# PicCan2.net
KiCad netlist of a schematic drawn in EAGLE
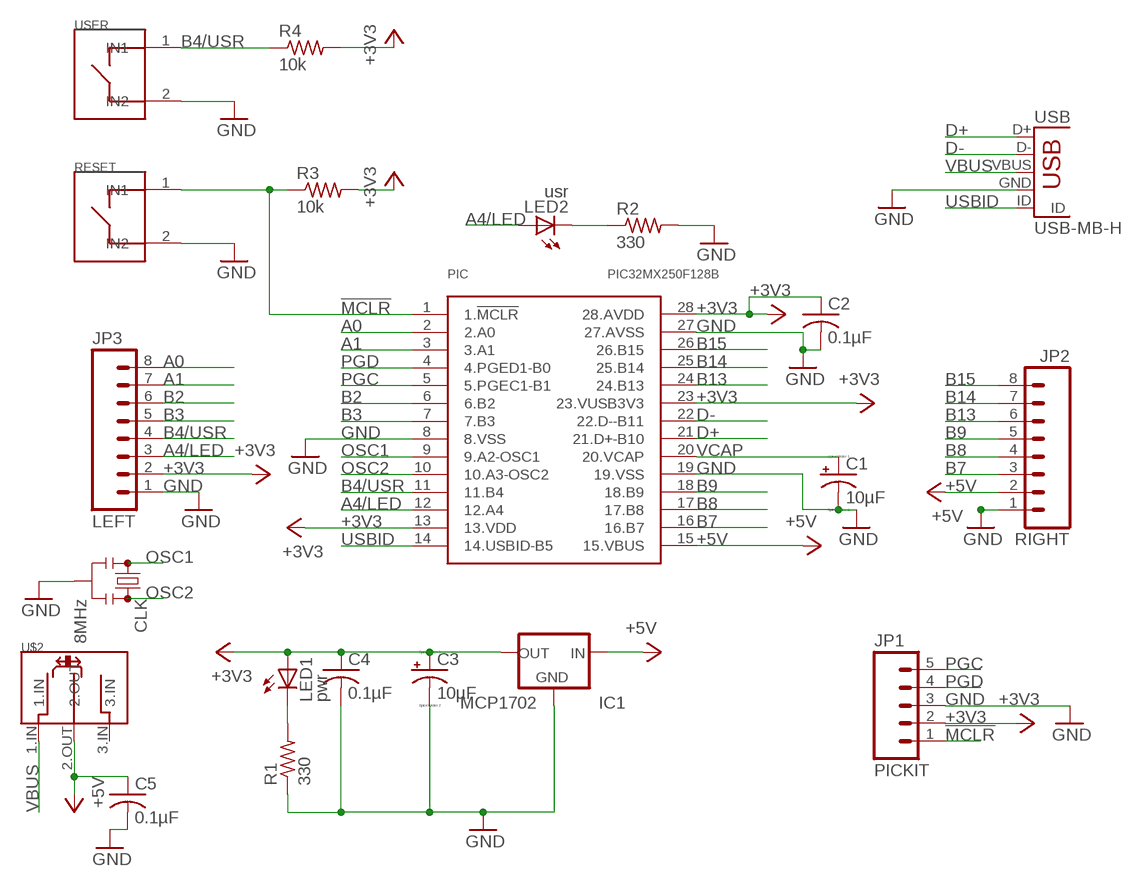
[diagram p0: schematic, sheet 1]

(export (version "E")
  (design (tool "Eeschema 10.0.6"))
  (components
    (comp (ref "C1")
      (value "10µF")
      (footprint "eagle-import:B45181A")
      (libsource (lib "eagle-import") (part "CPOL-USB45181A"))
    )
    (comp (ref "C2")
      (value "0.1µF")
      (footprint "eagle-import:C025-025X050")
      (libsource (lib "eagle-import") (part "C-US025-025X050"))
    )
    (comp (ref "C3")
      (value "10µF")
      (footprint "eagle-import:B45181A")
      (libsource (lib "eagle-import") (part "CPOL-USB45181A"))
    )
    (comp (ref "C4")
      (value "0.1µF")
      (footprint "eagle-import:C025-025X050")
      (libsource (lib "eagle-import") (part "C-US025-025X050"))
    )
    (comp (ref "C5")
      (value "0.1µF")
      (footprint "eagle-import:C025-025X050")
      (libsource (lib "eagle-import") (part "C-US025-025X050"))
    )
    (comp (ref "CLK")
      (value "8MHz")
      (footprint "eagle-import:RESONATOR-PTH")
      (libsource (lib "eagle-import") (part "RESONATORPTH"))
    )
    (comp (ref "IC1")
      (value "MCP1702")
      (footprint "eagle-import:79LXX")
      (libsource (lib "eagle-import") (part "79LXX"))
    )
    (comp (ref "JP1")
      (value "PICKIT")
      (footprint "eagle-import:1X05")
      (libsource (lib "eagle-import") (part "M05PTH"))
    )
    (comp (ref "JP2")
      (value "RIGHT")
      (footprint "eagle-import:1X08")
      (libsource (lib "eagle-import") (part "M08SILK_FEMALE_PTH"))
    )
    (comp (ref "JP3")
      (value "LEFT")
      (footprint "eagle-import:1X08")
      (libsource (lib "eagle-import") (part "M08SILK_FEMALE_PTH"))
    )
    (comp (ref "LED1")
      (value "pwr")
      (footprint "eagle-import:LED3MM")
      (libsource (lib "eagle-import") (part "LED3MM"))
    )
    (comp (ref "LED2")
      (value "usr")
      (footprint "eagle-import:LED3MM")
      (libsource (lib "eagle-import") (part "LED3MM"))
    )
    (comp (ref "PIC")
      (value "PIC32MX250F128B")
      (footprint "eagle-import:DIL28-3")
      (libsource (lib "eagle-import") (part "PIC32MX250F128B"))
    )
    (comp (ref "R1")
      (value "330")
      (footprint "eagle-import:0207_10")
      (libsource (lib "eagle-import") (part "R-US_0207/10"))
    )
    (comp (ref "R2")
      (value "330")
      (footprint "eagle-import:0207_10")
      (libsource (lib "eagle-import") (part "R-US_0207/10"))
    )
    (comp (ref "R3")
      (value "10k")
      (footprint "eagle-import:0207_10")
      (libsource (lib "eagle-import") (part "R-US_0207/10"))
    )
    (comp (ref "R4")
      (value "10k")
      (footprint "eagle-import:0207_10")
      (libsource (lib "eagle-import") (part "R-US_0207/10"))
    )
    (comp (ref "RESET")
      (value "PUSHBUTTON")
      (footprint "eagle-import:1X020")
      (libsource (lib "eagle-import") (part "PUSHBUTTON"))
    )
    (comp (ref "U$2")
      (value "SLDSWCH")
      (footprint "eagle-import:SLDSWCH")
      (libsource (lib "eagle-import") (part "SLDSWCH"))
    )
    (comp (ref "USB")
      (value "USB-MB-H")
      (footprint "eagle-import:USB-MB-H")
      (libsource (lib "eagle-import") (part "USB-MB-H"))
    )
    (comp (ref "USER")
      (value "PUSHBUTTON")
      (footprint "eagle-import:1X020")
      (libsource (lib "eagle-import") (part "PUSHBUTTON"))
    )
  )
  (nets
    (net (code "1") (name "+3V3") (class "Default")
      (node (ref "C2") (pin "1") (pinfunction "1_1") (pintype "passive"))
      (node (ref "C3") (pin "+") (pinfunction "+_+") (pintype "passive"))
      (node (ref "C4") (pin "1") (pinfunction "1_1") (pintype "passive"))
      (node (ref "IC1") (pin "OUT") (pinfunction "OUT_OUT") (pintype "passive"))
      (node (ref "JP1") (pin "2") (pinfunction "2_2") (pintype "passive"))
      (node (ref "JP3") (pin "2") (pinfunction "2_2") (pintype "passive"))
      (node (ref "LED1") (pin "A") (pinfunction "A_A") (pintype "passive"))
      (node (ref "PIC") (pin "13") (pinfunction "13.VDD_13") (pintype "bidirectional"))
      (node (ref "PIC") (pin "23") (pinfunction "23.VUSB3V3_23") (pintype "bidirectional"))
      (node (ref "PIC") (pin "28") (pinfunction "28.AVDD_28") (pintype "bidirectional"))
      (node (ref "R3") (pin "2") (pinfunction "2_2") (pintype "passive"))
      (node (ref "R4") (pin "2") (pinfunction "2_2") (pintype "passive"))
    )
    (net (code "2") (name "+5V") (class "Default")
      (node (ref "C5") (pin "1") (pinfunction "1_1") (pintype "passive"))
      (node (ref "IC1") (pin "IN") (pinfunction "IN_IN") (pintype "input"))
      (node (ref "JP2") (pin "2") (pinfunction "2_2") (pintype "passive"))
      (node (ref "PIC") (pin "15") (pinfunction "15.VBUS_15") (pintype "bidirectional"))
      (node (ref "U$2") (pin "2.OUT") (pinfunction "2.OUT_2.OUT") (pintype "bidirectional"))
    )
    (net (code "3") (name "/A0") (class "Default")
      (node (ref "JP3") (pin "8") (pinfunction "8_8") (pintype "passive"))
      (node (ref "PIC") (pin "2") (pinfunction "2.A0_2") (pintype "bidirectional"))
    )
    (net (code "4") (name "/A1") (class "Default")
      (node (ref "JP3") (pin "7") (pinfunction "7_7") (pintype "passive"))
      (node (ref "PIC") (pin "3") (pinfunction "3.A1_3") (pintype "bidirectional"))
    )
    (net (code "5") (name "/A4{slash}LED") (class "Default")
      (node (ref "JP3") (pin "3") (pinfunction "3_3") (pintype "passive"))
      (node (ref "LED2") (pin "A") (pinfunction "A_A") (pintype "passive"))
      (node (ref "PIC") (pin "12") (pinfunction "12.A4_12") (pintype "bidirectional"))
    )
    (net (code "6") (name "/B2") (class "Default")
      (node (ref "JP3") (pin "6") (pinfunction "6_6") (pintype "passive"))
      (node (ref "PIC") (pin "6") (pinfunction "6.B2_6") (pintype "bidirectional"))
    )
    (net (code "7") (name "/B3") (class "Default")
      (node (ref "JP3") (pin "5") (pinfunction "5_5") (pintype "passive"))
      (node (ref "PIC") (pin "7") (pinfunction "7.B3_7") (pintype "bidirectional"))
    )
    (net (code "8") (name "/B4{slash}USR") (class "Default")
      (node (ref "JP3") (pin "4") (pinfunction "4_4") (pintype "passive"))
      (node (ref "PIC") (pin "11") (pinfunction "11.B4_11") (pintype "bidirectional"))
      (node (ref "R4") (pin "1") (pinfunction "1_1") (pintype "passive"))
      (node (ref "USER") (pin "1") (pinfunction "IN1_1") (pintype "bidirectional"))
    )
    (net (code "9") (name "/B7") (class "Default")
      (node (ref "JP2") (pin "3") (pinfunction "3_3") (pintype "passive"))
      (node (ref "PIC") (pin "16") (pinfunction "16.B7_16") (pintype "bidirectional"))
    )
    (net (code "10") (name "/B8") (class "Default")
      (node (ref "JP2") (pin "4") (pinfunction "4_4") (pintype "passive"))
      (node (ref "PIC") (pin "17") (pinfunction "17.B8_17") (pintype "bidirectional"))
    )
    (net (code "11") (name "/B9") (class "Default")
      (node (ref "JP2") (pin "5") (pinfunction "5_5") (pintype "passive"))
      (node (ref "PIC") (pin "18") (pinfunction "18.B9_18") (pintype "bidirectional"))
    )
    (net (code "12") (name "/B13") (class "Default")
      (node (ref "JP2") (pin "6") (pinfunction "6_6") (pintype "passive"))
      (node (ref "PIC") (pin "24") (pinfunction "24.B13_24") (pintype "bidirectional"))
    )
    (net (code "13") (name "/B14") (class "Default")
      (node (ref "JP2") (pin "7") (pinfunction "7_7") (pintype "passive"))
      (node (ref "PIC") (pin "25") (pinfunction "25.B14_25") (pintype "bidirectional"))
    )
    (net (code "14") (name "/B15") (class "Default")
      (node (ref "JP2") (pin "8") (pinfunction "8_8") (pintype "passive"))
      (node (ref "PIC") (pin "26") (pinfunction "26.B15_26") (pintype "bidirectional"))
    )
    (net (code "15") (name "/D+") (class "Default")
      (node (ref "PIC") (pin "21") (pinfunction "21.D+-B10_21") (pintype "bidirectional"))
      (node (ref "USB") (pin "D+") (pinfunction "D+_D+") (pintype "bidirectional"))
    )
    (net (code "16") (name "/D-") (class "Default")
      (node (ref "PIC") (pin "22") (pinfunction "22.D--B11_22") (pintype "bidirectional"))
      (node (ref "USB") (pin "D-") (pinfunction "D-_D-") (pintype "bidirectional"))
    )
    (net (code "17") (name "/OSC1") (class "Default")
      (node (ref "CLK") (pin "1") (pinfunction "1_1") (pintype "passive"))
      (node (ref "PIC") (pin "9") (pinfunction "9.A2-OSC1_9") (pintype "bidirectional"))
    )
    (net (code "18") (name "/OSC2") (class "Default")
      (node (ref "CLK") (pin "3") (pinfunction "3_3") (pintype "passive"))
      (node (ref "PIC") (pin "10") (pinfunction "10.A3-OSC2_10") (pintype "bidirectional"))
    )
    (net (code "19") (name "/PGC") (class "Default")
      (node (ref "JP1") (pin "5") (pinfunction "5_5") (pintype "passive"))
      (node (ref "PIC") (pin "5") (pinfunction "5.PGEC1-B1_5") (pintype "bidirectional"))
    )
    (net (code "20") (name "/PGD") (class "Default")
      (node (ref "JP1") (pin "4") (pinfunction "4_4") (pintype "passive"))
      (node (ref "PIC") (pin "4") (pinfunction "4.PGED1-B0_4") (pintype "bidirectional"))
    )
    (net (code "21") (name "/USBID") (class "Default")
      (node (ref "PIC") (pin "14") (pinfunction "14.USBID-B5_14") (pintype "bidirectional"))
      (node (ref "USB") (pin "ID") (pinfunction "ID_ID") (pintype "bidirectional"))
    )
    (net (code "22") (name "/VBUS") (class "Default")
      (node (ref "U$2") (pin "1.IN") (pinfunction "1.IN_1.IN") (pintype "bidirectional"))
      (node (ref "USB") (pin "VBUS") (pinfunction "VBUS_VBUS") (pintype "bidirectional"))
    )
    (net (code "23") (name "/VCAP") (class "Default")
      (node (ref "C1") (pin "+") (pinfunction "+_+") (pintype "passive"))
      (node (ref "PIC") (pin "20") (pinfunction "20.VCAP_20") (pintype "bidirectional"))
    )
    (net (code "24") (name "/~{MCLR}") (class "Default")
      (node (ref "JP1") (pin "1") (pinfunction "1_1") (pintype "passive"))
      (node (ref "PIC") (pin "1") (pinfunction "1.~{MCLR}_1") (pintype "bidirectional"))
      (node (ref "R3") (pin "1") (pinfunction "1_1") (pintype "passive"))
      (node (ref "RESET") (pin "1") (pinfunction "IN1_1") (pintype "bidirectional"))
    )
    (net (code "25") (name "GND") (class "Default")
      (node (ref "C1") (pin "-") (pinfunction "-_-") (pintype "passive"))
      (node (ref "C2") (pin "2") (pinfunction "2_2") (pintype "passive"))
      (node (ref "C3") (pin "-") (pinfunction "-_-") (pintype "passive"))
      (node (ref "C4") (pin "2") (pinfunction "2_2") (pintype "passive"))
      (node (ref "C5") (pin "2") (pinfunction "2_2") (pintype "passive"))
      (node (ref "CLK") (pin "2") (pinfunction "2_2") (pintype "passive"))
      (node (ref "IC1") (pin "GND") (pinfunction "GND_GND") (pintype "input"))
      (node (ref "JP1") (pin "3") (pinfunction "3_3") (pintype "passive"))
      (node (ref "JP2") (pin "1") (pinfunction "1_1") (pintype "passive"))
      (node (ref "JP3") (pin "1") (pinfunction "1_1") (pintype "passive"))
      (node (ref "PIC") (pin "19") (pinfunction "19.VSS_19") (pintype "bidirectional"))
      (node (ref "PIC") (pin "27") (pinfunction "27.AVSS_27") (pintype "bidirectional"))
      (node (ref "PIC") (pin "8") (pinfunction "8.VSS_8") (pintype "bidirectional"))
      (node (ref "R1") (pin "1") (pinfunction "1_1") (pintype "passive"))
      (node (ref "R2") (pin "2") (pinfunction "2_2") (pintype "passive"))
      (node (ref "RESET") (pin "2") (pinfunction "IN2_2") (pintype "bidirectional"))
      (node (ref "USB") (pin "GND") (pinfunction "GND_GND") (pintype "bidirectional"))
      (node (ref "USER") (pin "2") (pinfunction "IN2_2") (pintype "bidirectional"))
    )
    (net (code "26") (name "Net-(LED1-C)") (class "Default")
      (node (ref "LED1") (pin "K") (pinfunction "C_K") (pintype "passive"))
      (node (ref "R1") (pin "2") (pinfunction "2_2") (pintype "passive"))
    )
    (net (code "27") (name "Net-(LED2-C)") (class "Default")
      (node (ref "LED2") (pin "K") (pinfunction "C_K") (pintype "passive"))
      (node (ref "R2") (pin "1") (pinfunction "1_1") (pintype "passive"))
    )
    (net (code "28") (name "unconnected-(U$2-Pad3.IN)") (class "Default")
      (node (ref "U$2") (pin "3.IN") (pinfunction "3.IN_3.IN") (pintype "bidirectional"))
    )
  )
)
